# synth-zodiac-sw-test.net
KiCad netlist of a schematic drawn in EAGLE
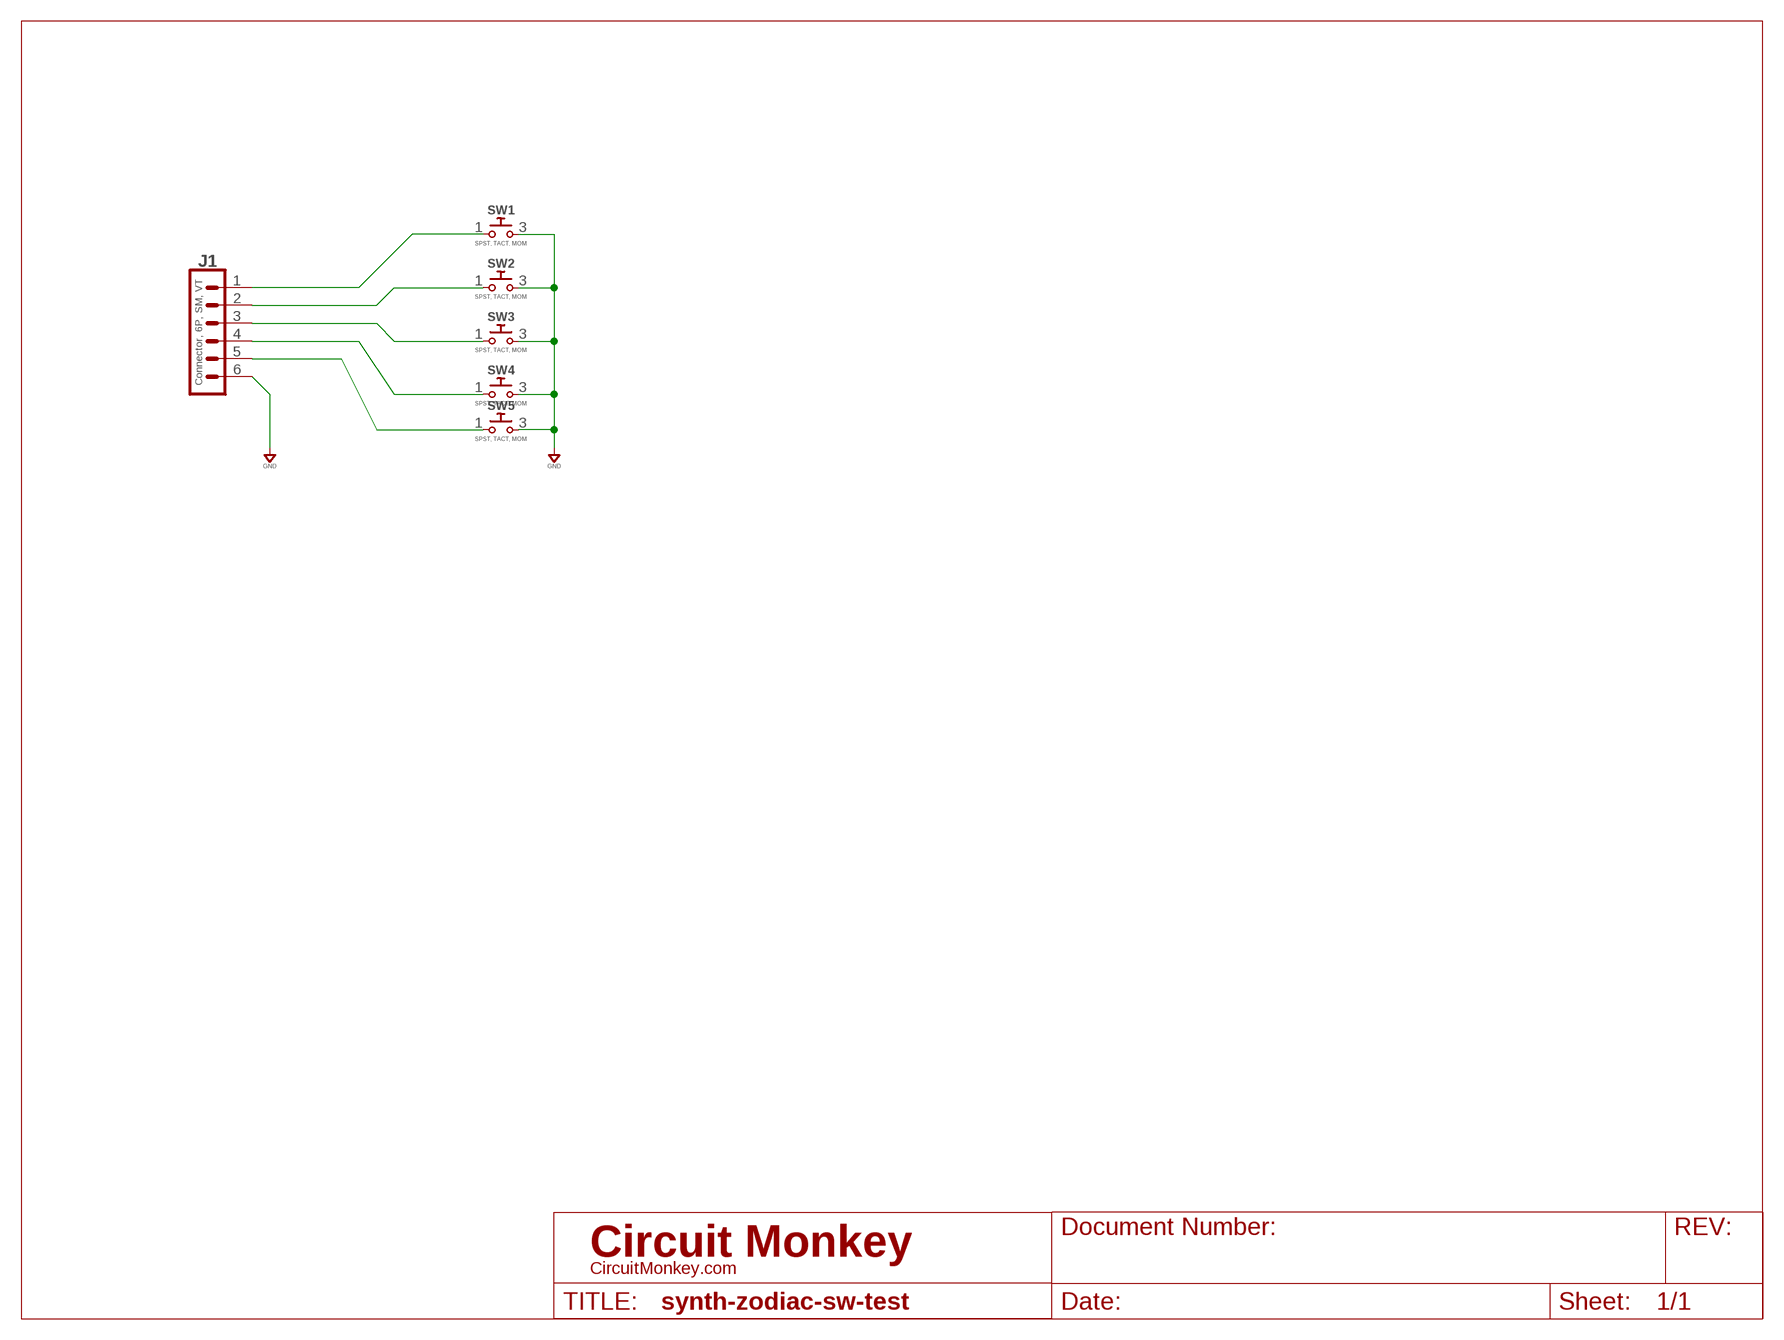
[diagram p0: schematic, sheet 1]

(export (version "E")
  (design (tool "Eeschema 10.0.6"))
  (components
    (comp (ref "J1")
      (value "Connector, 6P, SM, VT")
      (footprint "eagle-import:BM06B-SRSS-TB")
      (fields (field (name "MFR") "JST") (field (name "MPN") "BM06-SRSS-TB"))
      (libsource (lib "eagle-import") (part "06P-SM-VT-SMT"))
    )
    (comp (ref "SW1")
      (value "SPST, TACT, MOM")
      (footprint "eagle-import:B3FS-BACKMOUNT")
      (fields (field (name "MFR") "CK") (field (name "MPN") "B3FS"))
      (libsource (lib "eagle-import") (part "PUSHBTN-MOMB3FS-BLIND"))
    )
    (comp (ref "SW2")
      (value "SPST, TACT, MOM")
      (footprint "eagle-import:B3FS-BACKMOUNT")
      (fields (field (name "MFR") "CK") (field (name "MPN") "B3FS"))
      (libsource (lib "eagle-import") (part "PUSHBTN-MOMB3FS-BLIND"))
    )
    (comp (ref "SW3")
      (value "SPST, TACT, MOM")
      (footprint "eagle-import:B3FS-BACKMOUNT")
      (fields (field (name "MFR") "CK") (field (name "MPN") "B3FS"))
      (libsource (lib "eagle-import") (part "PUSHBTN-MOMB3FS-BLIND"))
    )
    (comp (ref "SW4")
      (value "SPST, TACT, MOM")
      (footprint "eagle-import:B3FS-BACKMOUNT")
      (fields (field (name "MFR") "CK") (field (name "MPN") "B3FS"))
      (libsource (lib "eagle-import") (part "PUSHBTN-MOMB3FS-BLIND"))
    )
    (comp (ref "SW5")
      (value "SPST, TACT, MOM")
      (footprint "eagle-import:B3FS-BACKMOUNT")
      (fields (field (name "MFR") "CK") (field (name "MPN") "B3FS"))
      (libsource (lib "eagle-import") (part "PUSHBTN-MOMB3FS-BLIND"))
    )
  )
  (nets
    (net (code "1") (name "GND") (class "Default")
      (node (ref "J1") (pin "6") (pinfunction "6_6") (pintype "passive"))
      (node (ref "SW1") (pin "3") (pinfunction "2_3") (pintype "passive"))
      (node (ref "SW2") (pin "3") (pinfunction "2_3") (pintype "passive"))
      (node (ref "SW3") (pin "3") (pinfunction "2_3") (pintype "passive"))
      (node (ref "SW4") (pin "3") (pinfunction "2_3") (pintype "passive"))
      (node (ref "SW5") (pin "3") (pinfunction "2_3") (pintype "passive"))
    )
    (net (code "2") (name "Net-(J1-Pad1)") (class "Default")
      (node (ref "J1") (pin "1") (pinfunction "1_1") (pintype "passive"))
      (node (ref "SW1") (pin "1") (pinfunction "1_1") (pintype "passive"))
    )
    (net (code "3") (name "Net-(J1-Pad2)") (class "Default")
      (node (ref "J1") (pin "2") (pinfunction "2_2") (pintype "passive"))
      (node (ref "SW2") (pin "1") (pinfunction "1_1") (pintype "passive"))
    )
    (net (code "4") (name "Net-(J1-Pad3)") (class "Default")
      (node (ref "J1") (pin "3") (pinfunction "3_3") (pintype "passive"))
      (node (ref "SW3") (pin "1") (pinfunction "1_1") (pintype "passive"))
    )
    (net (code "5") (name "Net-(J1-Pad4)") (class "Default")
      (node (ref "J1") (pin "4") (pinfunction "4_4") (pintype "passive"))
      (node (ref "SW4") (pin "1") (pinfunction "1_1") (pintype "passive"))
    )
    (net (code "6") (name "Net-(J1-Pad5)") (class "Default")
      (node (ref "J1") (pin "5") (pinfunction "5_5") (pintype "passive"))
      (node (ref "SW5") (pin "1") (pinfunction "1_1") (pintype "passive"))
    )
  )
)
